# 1_power.net
KiCad netlist of a schematic drawn in Altium Designer
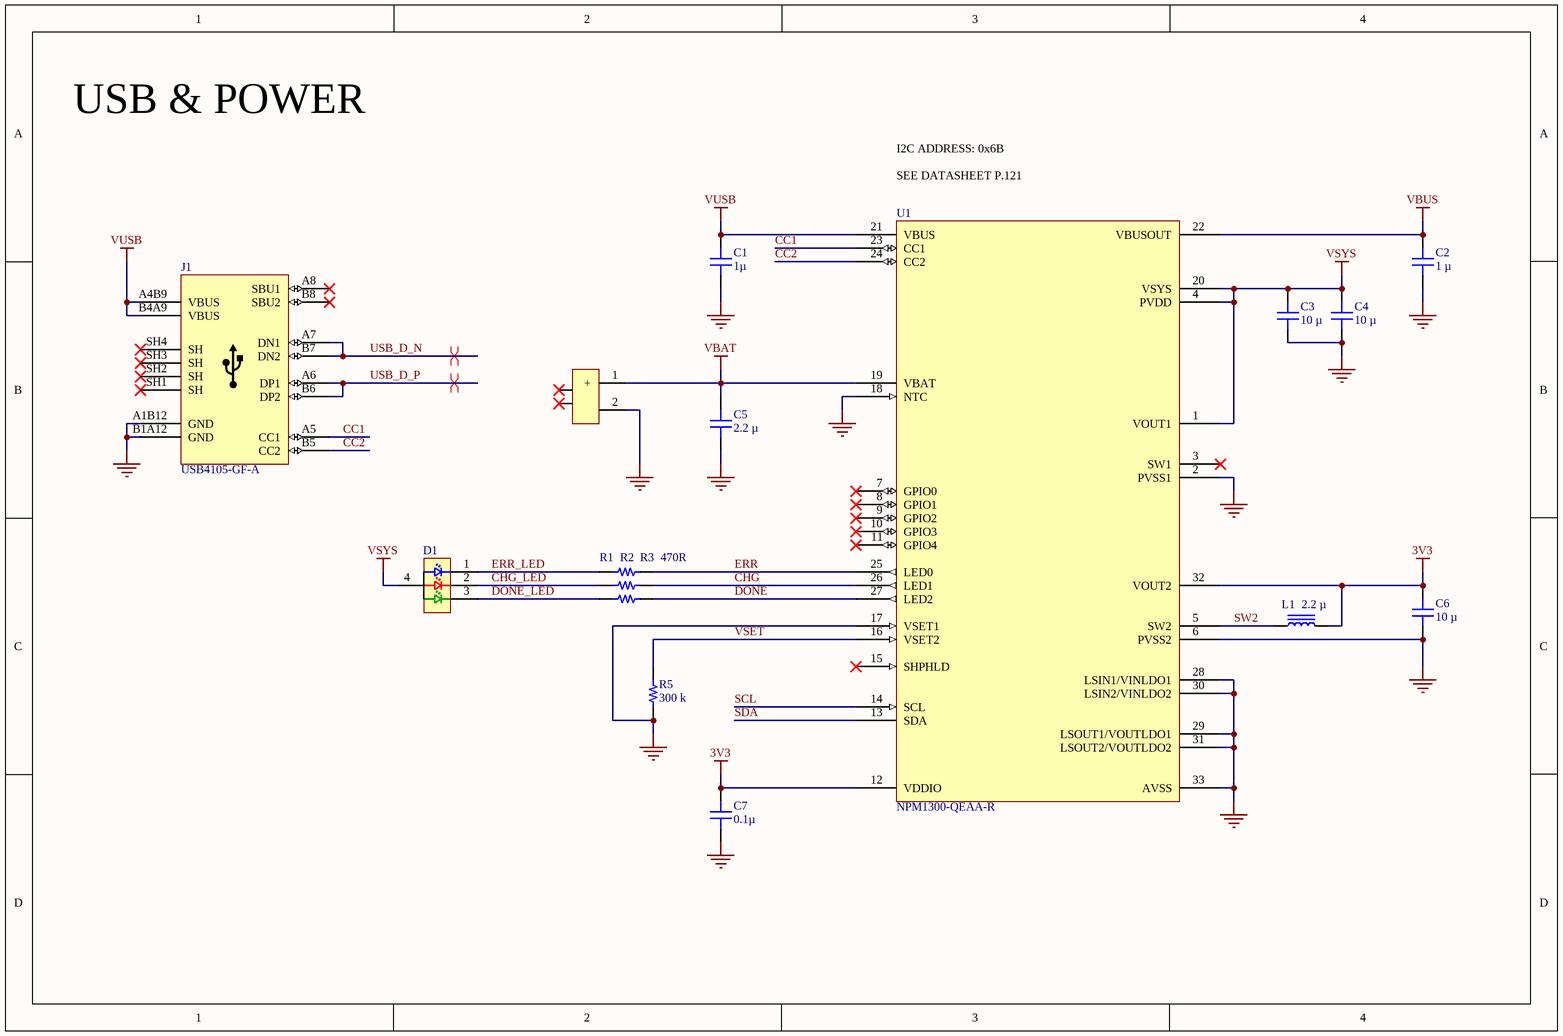
[diagram p0: 1_power.SchDoc]

(export (version "E")
  (design (tool "Eeschema 10.0.6"))
  (components
    (comp (ref "C1")
      (value "1µ")
      (footprint "CAP 0402_1005")
      (description "CAP CER 1UF 10V X5R 0402")
      (fields (field (name "PART NUMBER") "885012105012") (field (name "MANUFACTURER") "Würth Elektronik"))
      (libsource (lib "Celestial Altium Library - altium_library") (part "Capacitor"))
    )
    (comp (ref "C2")
      (value "1 µ")
      (footprint "CAP 0402_1005")
      (description "CAP CER 1UF 10V X5R 0402")
      (fields (field (name "PART NUMBER") "885012105012") (field (name "MANUFACTURER") "Würth Elektronik"))
      (libsource (lib "Celestial Altium Library - altium_library") (part "Capacitor"))
    )
    (comp (ref "C3")
      (value "10 µ")
      (footprint "CAP 0402_1005")
      (description "CAP CER 10UF 10V X5R 0402")
      (fields
        (field (name "PART NUMBER") "CL05A106MP8NUB8")
        (field (name "MANUFACTURER") "Samsung Electro-Mechanics")
      )
      (libsource (lib "Celestial Altium Library - altium_library") (part "Capacitor"))
    )
    (comp (ref "C4")
      (value "10 µ")
      (footprint "CAP 0402_1005")
      (description "CAP CER 10UF 10V X5R 0402")
      (fields
        (field (name "PART NUMBER") "CL05A106MP8NUB8")
        (field (name "MANUFACTURER") "Samsung Electro-Mechanics")
      )
      (libsource (lib "Celestial Altium Library - altium_library") (part "Capacitor"))
    )
    (comp (ref "C5")
      (value "2.2 µ")
      (footprint "CAP 0402_1005")
      (description "CAP CER 2.2UF 25V X5R 0402")
      (fields (field (name "PART NUMBER") "TMK105CBJ225KV-F") (field (name "MANUFACTURER") "Taiyo Yuden"))
      (libsource (lib "Celestial Altium Library - altium_library") (part "Capacitor"))
    )
    (comp (ref "C6")
      (value "10 µ")
      (footprint "CAP 0402_1005")
      (description "CAP CER 10UF 10V X5R 0402")
      (fields
        (field (name "PART NUMBER") "CL05A106MP8NUB8")
        (field (name "MANUFACTURER") "Samsung Electro-Mechanics")
      )
      (libsource (lib "Celestial Altium Library - altium_library") (part "Capacitor"))
    )
    (comp (ref "C7")
      (value "0.1µ")
      (footprint "CAP 0402_1005")
      (description "CAP CER 0.1UF 10V X7R 0402")
      (fields (field (name "PART NUMBER") "0402ZC104KAT2A") (field (name "MANUFACTURER") "AVX Corporation"))
      (libsource (lib "Celestial Altium Library - altium_library") (part "Capacitor"))
    )
    (comp (ref "D1")
      (value "Red, Green, Blue (RGB)")
      (footprint "Citizen CL-505S-X-SD-T")
      (description "LED TRI TOP FIRING 1.0 X 1.0")
      (fields (field (name "PART NUMBER") "CL-505S-X-SD-T") (field (name "MANUFACTURER") "Citizen"))
      (libsource (lib "Celestial Altium Library - altium_library") (part "RGB LED Citizen CL-505"))
    )
    (comp (ref "J1")
      (value "USB4105-GF-A")
      (footprint "GCT_USB4105-GF-A")
      (libsource (lib "University of South Florida") (part "USB4105-GF-A"))
    )
    (comp (ref "J2")
      (value "T1M-02-T-SH-L-K")
      (footprint "SAMTEC_T1M-02-T-SH-L-K")
      (description "1mm JST Connector, surface mounted, horizontal orientation.")
      (libsource (lib "University of South Florida") (part "T1M-02-T-SH-L-K"))
    )
    (comp (ref "L1")
      (value "2.2 µ")
      (footprint "IND 0402_1005")
      (description "IND  2.2UH  1.7OHM  10MA")
      (fields
        (field (name "PART NUMBER") "FCI1005F-2R2M")
        (field (name "MANUFACTURER") "TAI-TECH Advanced Electronics Co., Ltd.")
      )
      (libsource (lib "Celestial Altium Library - altium_library") (part "Inductor"))
    )
    (comp (ref "R1")
      (value "470R")
      (footprint "RES 0402_1005")
      (description "RES 470 OHM 0.1% 1/16W 0402")
      (fields (field (name "PART NUMBER") "TNPW0402470RBYEP") (field (name "MANUFACTURER") "Vishay Dale"))
      (libsource (lib "Celestial Altium Library - altium_library") (part "Resistor"))
    )
    (comp (ref "R2")
      (value "470 Ohms")
      (footprint "RES 0402_1005")
      (description "RES 470 OHM 0.1% 1/16W 0402")
      (fields (field (name "PART NUMBER") "TNPW0402470RBYEP") (field (name "MANUFACTURER") "Vishay Dale"))
      (libsource (lib "Celestial Altium Library - altium_library") (part "Resistor"))
    )
    (comp (ref "R3")
      (value "470 Ohms")
      (footprint "RES 0402_1005")
      (description "RES 470 OHM 0.1% 1/16W 0402")
      (fields (field (name "PART NUMBER") "TNPW0402470RBYEP") (field (name "MANUFACTURER") "Vishay Dale"))
      (libsource (lib "Celestial Altium Library - altium_library") (part "Resistor"))
    )
    (comp (ref "R5")
      (value "300 k")
      (footprint "RES 0402_1005")
      (description "RES 300K OHM 5% 1/16W 0402")
      (fields (field (name "PART NUMBER") "RC0402JR-07300KL") (field (name "MANUFACTURER") "Yageo"))
      (libsource (lib "Celestial Altium Library - altium_library") (part "Resistor"))
    )
    (comp (ref "U1")
      (value "NPM1300-QEAA-R")
      (footprint "Nordic_QFN50P500X500X90-33N")
      (description "Battery Power Management IC Lithium Ion/Polymer 32-QFN (5x5)")
      (fields (field (name "JLCPCB PART #") "C7466043"))
      (libsource (lib "University of South Florida") (part "nPM1300-QEAA"))
    )
  )
  (nets
    (net (code "1") (name "/CC1") (class "Default")
      (node (ref "J1") (pin "A5") (pinfunction "CC1_A5") (pintype "bidirectional"))
      (node (ref "U1") (pin "23") (pinfunction "CC1_23") (pintype "bidirectional"))
    )
    (net (code "2") (name "/CC2") (class "Default")
      (node (ref "J1") (pin "B5") (pinfunction "CC2_B5") (pintype "bidirectional"))
      (node (ref "U1") (pin "24") (pinfunction "CC2_24") (pintype "bidirectional"))
    )
    (net (code "3") (name "/CHG") (class "Default")
      (node (ref "R2") (pin "2") (pinfunction "2_2") (pintype "passive"))
      (node (ref "U1") (pin "26") (pinfunction "LED1_26") (pintype "output"))
    )
    (net (code "4") (name "/CHG_LED") (class "Default")
      (node (ref "D1") (pin "2") (pinfunction "C2_2") (pintype "passive"))
      (node (ref "R2") (pin "1") (pinfunction "1_1") (pintype "passive"))
    )
    (net (code "5") (name "/DONE") (class "Default")
      (node (ref "R3") (pin "2") (pinfunction "2_2") (pintype "passive"))
      (node (ref "U1") (pin "27") (pinfunction "LED2_27") (pintype "output"))
    )
    (net (code "6") (name "/DONE_LED") (class "Default")
      (node (ref "D1") (pin "3") (pinfunction "C3_3") (pintype "passive"))
      (node (ref "R3") (pin "1") (pinfunction "1_1") (pintype "passive"))
    )
    (net (code "7") (name "/ERR") (class "Default")
      (node (ref "R1") (pin "2") (pinfunction "2_2") (pintype "passive"))
      (node (ref "U1") (pin "25") (pinfunction "LED0_25") (pintype "output"))
    )
    (net (code "8") (name "/ERR_LED") (class "Default")
      (node (ref "D1") (pin "1") (pinfunction "C1_1") (pintype "passive"))
      (node (ref "R1") (pin "1") (pinfunction "1_1") (pintype "passive"))
    )
    (net (code "9") (name "/SCL") (class "Default")
      (node (ref "U1") (pin "14") (pinfunction "SCL_14") (pintype "input"))
    )
    (net (code "10") (name "/SDA") (class "Default")
      (node (ref "U1") (pin "13") (pinfunction "SDA_13") (pintype "open_collector"))
    )
    (net (code "11") (name "/SW2") (class "Default")
      (node (ref "L1") (pin "1") (pinfunction "1_1") (pintype "passive"))
      (node (ref "U1") (pin "5") (pinfunction "SW2_5") (pintype "power_in"))
    )
    (net (code "12") (name "/USB_D_N") (class "Default")
      (node (ref "J1") (pin "A7") (pinfunction "DN1_A7") (pintype "bidirectional"))
      (node (ref "J1") (pin "B7") (pinfunction "DN2_B7") (pintype "bidirectional"))
    )
    (net (code "13") (name "/USB_D_P") (class "Default")
      (node (ref "J1") (pin "A6") (pinfunction "DP1_A6") (pintype "bidirectional"))
      (node (ref "J1") (pin "B6") (pinfunction "DP2_B6") (pintype "bidirectional"))
    )
    (net (code "14") (name "/VSET") (class "Default")
      (node (ref "R5") (pin "2") (pinfunction "2_2") (pintype "passive"))
      (node (ref "U1") (pin "16") (pinfunction "VSET2_16") (pintype "input"))
    )
    (net (code "15") (name "3V3") (class "Default")
      (node (ref "C6") (pin "2") (pinfunction "2_2") (pintype "passive"))
      (node (ref "C7") (pin "2") (pinfunction "2_2") (pintype "passive"))
      (node (ref "L1") (pin "2") (pinfunction "2_2") (pintype "passive"))
      (node (ref "U1") (pin "12") (pinfunction "VDDIO_12") (pintype "power_in"))
      (node (ref "U1") (pin "32") (pinfunction "VOUT2_32") (pintype "power_in"))
    )
    (net (code "16") (name "GND") (class "Default")
      (node (ref "C1") (pin "1") (pinfunction "1_1") (pintype "passive"))
      (node (ref "C2") (pin "1") (pinfunction "1_1") (pintype "passive"))
      (node (ref "C3") (pin "2") (pinfunction "2_2") (pintype "passive"))
      (node (ref "C4") (pin "2") (pinfunction "2_2") (pintype "passive"))
      (node (ref "C5") (pin "1") (pinfunction "1_1") (pintype "passive"))
      (node (ref "C6") (pin "1") (pinfunction "1_1") (pintype "passive"))
      (node (ref "C7") (pin "1") (pinfunction "1_1") (pintype "passive"))
      (node (ref "J1") (pin "A1B12") (pinfunction "GND_A1B12") (pintype "power_in"))
      (node (ref "J1") (pin "B1A12") (pinfunction "GND_B1A12") (pintype "power_in"))
      (node (ref "J2") (pin "2") (pinfunction "2_2") (pintype "power_in"))
      (node (ref "R5") (pin "1") (pinfunction "1_1") (pintype "passive"))
      (node (ref "U1") (pin "17") (pinfunction "VSET1_17") (pintype "input"))
      (node (ref "U1") (pin "18") (pinfunction "NTC_18") (pintype "input"))
      (node (ref "U1") (pin "2") (pinfunction "PVSS1_2") (pintype "power_in"))
      (node (ref "U1") (pin "28") (pinfunction "LSIN1/VINLDO1_28") (pintype "power_in"))
      (node (ref "U1") (pin "29") (pinfunction "LSOUT1/VOUTLDO1_29") (pintype "power_in"))
      (node (ref "U1") (pin "30") (pinfunction "LSIN2/VINLDO2_30") (pintype "power_in"))
      (node (ref "U1") (pin "31") (pinfunction "LSOUT2/VOUTLDO2_31") (pintype "power_in"))
      (node (ref "U1") (pin "33") (pinfunction "AVSS_33") (pintype "power_in"))
      (node (ref "U1") (pin "6") (pinfunction "PVSS2_6") (pintype "power_in"))
    )
    (net (code "17") (name "VBAT") (class "Default")
      (node (ref "C5") (pin "2") (pinfunction "2_2") (pintype "passive"))
      (node (ref "J2") (pin "1") (pinfunction "+_1") (pintype "power_in"))
      (node (ref "U1") (pin "19") (pinfunction "VBAT_19") (pintype "passive"))
    )
    (net (code "18") (name "VBUS") (class "Default")
      (node (ref "C2") (pin "2") (pinfunction "2_2") (pintype "passive"))
      (node (ref "U1") (pin "22") (pinfunction "VBUSOUT_22") (pintype "power_in"))
    )
    (net (code "19") (name "VSYS") (class "Default")
      (node (ref "C3") (pin "1") (pinfunction "1_1") (pintype "passive"))
      (node (ref "C4") (pin "1") (pinfunction "1_1") (pintype "passive"))
      (node (ref "D1") (pin "4") (pinfunction "A3_4") (pintype "passive"))
      (node (ref "U1") (pin "1") (pinfunction "VOUT1_1") (pintype "power_in"))
      (node (ref "U1") (pin "20") (pinfunction "VSYS_20") (pintype "power_in"))
      (node (ref "U1") (pin "4") (pinfunction "PVDD_4") (pintype "power_in"))
    )
    (net (code "20") (name "VUSB") (class "Default")
      (node (ref "C1") (pin "2") (pinfunction "2_2") (pintype "passive"))
      (node (ref "J1") (pin "A4B9") (pinfunction "VBUS_A4B9") (pintype "power_in"))
      (node (ref "J1") (pin "B4A9") (pinfunction "VBUS_B4A9") (pintype "power_in"))
      (node (ref "U1") (pin "21") (pinfunction "VBUS_21") (pintype "power_in"))
    )
    (net (code "21") (name "unconnected-(J1-SBU1-PadA8)") (class "Default")
      (node (ref "J1") (pin "A8") (pinfunction "SBU1_A8") (pintype "bidirectional+no_connect"))
    )
    (net (code "22") (name "unconnected-(J1-SBU2-PadB8)") (class "Default")
      (node (ref "J1") (pin "B8") (pinfunction "SBU2_B8") (pintype "bidirectional+no_connect"))
    )
    (net (code "23") (name "unconnected-(J1-SH-PadSH1)") (class "Default")
      (node (ref "J1") (pin "SH1") (pinfunction "SH_SH1") (pintype "power_in+no_connect"))
    )
    (net (code "24") (name "unconnected-(J1-SH-PadSH2)") (class "Default")
      (node (ref "J1") (pin "SH2") (pinfunction "SH_SH2") (pintype "power_in+no_connect"))
    )
    (net (code "25") (name "unconnected-(J1-SH-PadSH3)") (class "Default")
      (node (ref "J1") (pin "SH3") (pinfunction "SH_SH3") (pintype "power_in+no_connect"))
    )
    (net (code "26") (name "unconnected-(J1-SH-PadSH4)") (class "Default")
      (node (ref "J1") (pin "SH4") (pinfunction "SH_SH4") (pintype "power_in+no_connect"))
    )
    (net (code "27") (name "unconnected-(J2-NC-PadS1)") (class "Default")
      (node (ref "J2") (pin "S1") (pinfunction "NC_S1") (pintype "passive+no_connect"))
    )
    (net (code "28") (name "unconnected-(J2-NC-PadS2)") (class "Default")
      (node (ref "J2") (pin "S2") (pinfunction "NC_S2") (pintype "passive+no_connect"))
    )
    (net (code "29") (name "unconnected-(U1-GPIO0-Pad7)") (class "Default")
      (node (ref "U1") (pin "7") (pinfunction "GPIO0_7") (pintype "bidirectional+no_connect"))
    )
    (net (code "30") (name "unconnected-(U1-GPIO1-Pad8)") (class "Default")
      (node (ref "U1") (pin "8") (pinfunction "GPIO1_8") (pintype "bidirectional+no_connect"))
    )
    (net (code "31") (name "unconnected-(U1-GPIO2-Pad9)") (class "Default")
      (node (ref "U1") (pin "9") (pinfunction "GPIO2_9") (pintype "bidirectional+no_connect"))
    )
    (net (code "32") (name "unconnected-(U1-GPIO3-Pad10)") (class "Default")
      (node (ref "U1") (pin "10") (pinfunction "GPIO3_10") (pintype "bidirectional+no_connect"))
    )
    (net (code "33") (name "unconnected-(U1-GPIO4-Pad11)") (class "Default")
      (node (ref "U1") (pin "11") (pinfunction "GPIO4_11") (pintype "bidirectional+no_connect"))
    )
    (net (code "34") (name "unconnected-(U1-SHPHLD-Pad15)") (class "Default")
      (node (ref "U1") (pin "15") (pinfunction "SHPHLD_15") (pintype "input+no_connect"))
    )
    (net (code "35") (name "unconnected-(U1-SW1-Pad3)") (class "Default")
      (node (ref "U1") (pin "3") (pinfunction "SW1_3") (pintype "power_in+no_connect"))
    )
  )
)
